# Air_SCHv3.net
KiCad netlist of a schematic drawn in Altium Designer
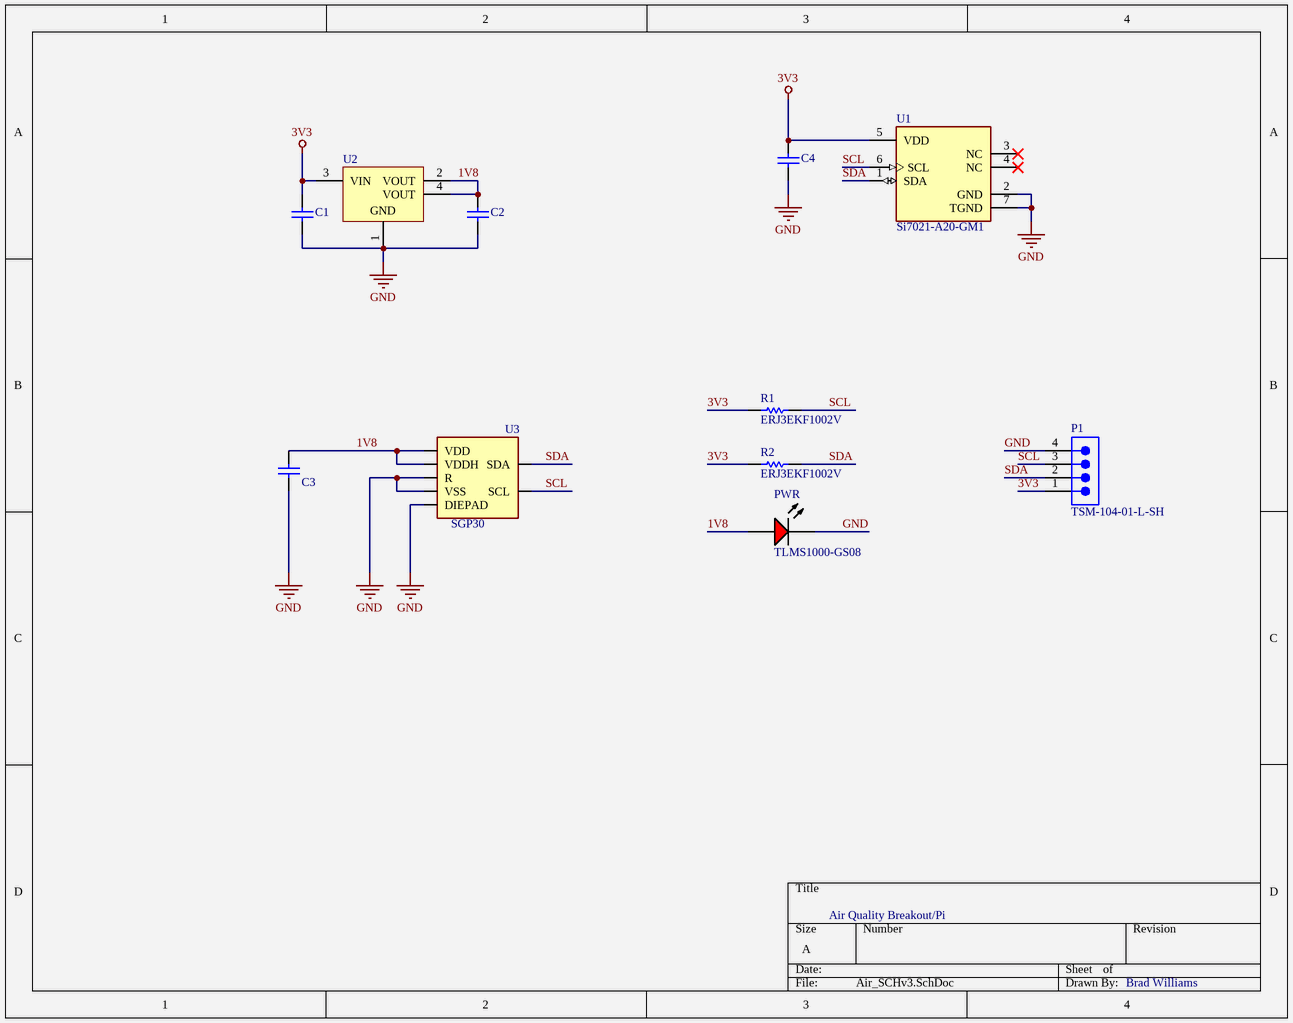
[diagram p0: Air_SCHv3.SchDoc]

(export (version "E")
  (design (tool "Eeschema 10.0.6"))
  (components
    (comp (ref "C1")
      (value "CGA3E2X7R1H104K080AA")
      (footprint "CAPC1608X90X20LL10")
      (description "Chip Capacitor, 0.1 uF, +/- 10%, 50 V, -55 to 125 degC, 0603 (1608 Metric), RoHS, Tape and Reel")
      (fields (field (name "VOLTAGE") "50V") (field (name "TOLERANCE") "10%"))
      (libsource (lib "Altium Content Vault") (part "CAP-NP-2"))
    )
    (comp (ref "C2")
      (value "GCM21BR70J106KE22L")
      (footprint "CAPC2013X140X45LL15T25")
      (fields (field (name "MANUFACTURER") "Murata"))
      (libsource (lib "Altium Content Vault") (part "CAP"))
    )
    (comp (ref "C3")
      (value "CGA3E2X7R1H104K080AA")
      (footprint "CAPC1608X90X20LL10")
      (description "Chip Capacitor, 0.1 uF, +/- 10%, 50 V, -55 to 125 degC, 0603 (1608 Metric), RoHS, Tape and Reel")
      (fields (field (name "VOLTAGE") "50V") (field (name "TOLERANCE") "10%"))
      (libsource (lib "Altium Content Vault") (part "CAP-NP-2"))
    )
    (comp (ref "C4")
      (value "CGA3E2X7R1H104K080AA")
      (footprint "CAPC1608X90X20LL10")
      (description "Chip Capacitor, 0.1 uF, +/- 10%, 50 V, -55 to 125 degC, 0603 (1608 Metric), RoHS, Tape and Reel")
      (fields (field (name "VOLTAGE") "50V") (field (name "TOLERANCE") "10%"))
      (libsource (lib "Altium Content Vault") (part "CAP-NP-2"))
    )
    (comp (ref "P1")
      (value "TSM-104-01-L-SH")
      (footprint "SMTC-TSM-104-01-X-SH")
      (fields (field (name "MANUFACTURER") "Samtec"))
      (libsource (lib "Altium Content Vault") (part "SMTC-TSM-104-01-X-SH"))
    )
    (comp (ref "PWR")
      (value "TLMS1000-GS08")
      (footprint "VISH-TLMS1000_V")
      (description "Low Current LED, 40 mW, 1.8 V, -40 to 100 degC, 2-Pin SMD (0603), RoHS, Tape and Reel")
      (fields (field (name "MANUFACTURER") "Vishay"))
      (libsource (lib "Altium Content Vault") (part "LED-RED-AK-2"))
    )
    (comp (ref "R1")
      (value "ERJ3EKF1002V")
      (footprint "RESC1609X55X30LL15T15")
      (description "Chip Resistor, 10 KOhm, +/- 1%, 0.1 W, -55 to 155 degC, 0603 (1608 Metric), RoHS, Tape and Reel")
      (fields (field (name "TOLERANCE") "1%") (field (name "MANUFACTURER") "Panasonic"))
      (libsource (lib "Altium Content Vault") (part "RES-2"))
    )
    (comp (ref "R2")
      (value "ERJ3EKF1002V")
      (footprint "RESC1609X55X30LL15T15")
      (description "Chip Resistor, 10 KOhm, +/- 1%, 0.1 W, -55 to 155 degC, 0603 (1608 Metric), RoHS, Tape and Reel")
      (fields (field (name "TOLERANCE") "1%") (field (name "MANUFACTURER") "Panasonic"))
      (libsource (lib "Altium Content Vault") (part "RES-2"))
    )
    (comp (ref "U1")
      (value "Si7021-A20-GM1")
      (footprint "FP-Si7021-A20-GM1-MFG")
      (description "SENS HUMI/TEMP 3.6V I2C 3% 6DFN")
      (libsource (lib "Altium Content Vault") (part "6f1d054818c6c7d664b89c5ab42d61f"))
    )
    (comp (ref "U2")
      (value "LD1117AS18TR")
      (footprint "SOT-223_L")
      (description "1A, Low Drop Positive Voltage Regulator, 1.8V, 4-Pin SOT-223, Tape and Reel")
      (libsource (lib "Altium Content Vault") (part "PM-REG-LD1117-SOT4"))
    )
    (comp (ref "U3")
      (value "SGP30")
      (footprint "SGP30")
      (description "AIR QUALITY GAS SENSOR FOR VOC'S")
      (fields (field (name "MF") "Sensirion AG"))
      (libsource (lib "Brad Williams") (part "SGP30"))
    )
  )
  (nets
    (net (code "1") (name "/1V8") (class "Default")
      (node (ref "C2") (pin "2") (pinfunction "2_2") (pintype "passive"))
      (node (ref "C3") (pin "2") (pinfunction "2_2") (pintype "passive"))
      (node (ref "PWR") (pin "1") (pinfunction "A_1") (pintype "passive"))
      (node (ref "U2") (pin "2") (pinfunction "VOUT_2") (pintype "power_in"))
      (node (ref "U2") (pin "4") (pinfunction "VOUT_4") (pintype "power_in"))
      (node (ref "U3") (pin "1") (pinfunction "VDD_1") (pintype "bidirectional"))
      (node (ref "U3") (pin "5") (pinfunction "VDDH_5") (pintype "bidirectional"))
    )
    (net (code "2") (name "/SCL") (class "Default")
      (node (ref "P1") (pin "3") (pinfunction "3_3") (pintype "passive"))
      (node (ref "R1") (pin "2") (pinfunction "2_2") (pintype "passive"))
      (node (ref "U1") (pin "6") (pinfunction "SCL_6") (pintype "input"))
      (node (ref "U3") (pin "6") (pinfunction "SCL_6") (pintype "bidirectional"))
    )
    (net (code "3") (name "/SDA") (class "Default")
      (node (ref "P1") (pin "2") (pinfunction "2_2") (pintype "passive"))
      (node (ref "R2") (pin "2") (pinfunction "2_2") (pintype "passive"))
      (node (ref "U1") (pin "1") (pinfunction "SDA_1") (pintype "bidirectional"))
      (node (ref "U3") (pin "3") (pinfunction "SDA_3") (pintype "bidirectional"))
    )
    (net (code "4") (name "3V3") (class "Default")
      (node (ref "C1") (pin "2") (pinfunction "2_2") (pintype "passive"))
      (node (ref "C4") (pin "2") (pinfunction "2_2") (pintype "passive"))
      (node (ref "P1") (pin "1") (pinfunction "1_1") (pintype "passive"))
      (node (ref "R1") (pin "1") (pinfunction "1_1") (pintype "passive"))
      (node (ref "R2") (pin "1") (pinfunction "1_1") (pintype "passive"))
      (node (ref "U1") (pin "5") (pinfunction "VDD_5") (pintype "power_in"))
      (node (ref "U2") (pin "3") (pinfunction "VIN_3") (pintype "power_in"))
    )
    (net (code "5") (name "GND") (class "Default")
      (node (ref "C1") (pin "1") (pinfunction "1_1") (pintype "passive"))
      (node (ref "C2") (pin "1") (pinfunction "1_1") (pintype "passive"))
      (node (ref "C3") (pin "1") (pinfunction "1_1") (pintype "passive"))
      (node (ref "C4") (pin "1") (pinfunction "1_1") (pintype "passive"))
      (node (ref "P1") (pin "4") (pinfunction "4_4") (pintype "passive"))
      (node (ref "PWR") (pin "2") (pinfunction "K_2") (pintype "passive"))
      (node (ref "U1") (pin "2") (pinfunction "GND_2") (pintype "power_in"))
      (node (ref "U1") (pin "7") (pinfunction "TGND_7") (pintype "power_in"))
      (node (ref "U2") (pin "1") (pinfunction "GND_1") (pintype "power_in"))
      (node (ref "U3") (pin "2") (pinfunction "VSS_2") (pintype "bidirectional"))
      (node (ref "U3") (pin "4") (pinfunction "R_4") (pintype "bidirectional"))
      (node (ref "U3") (pin "DIEPAD") (pinfunction "DIEPAD_DIEPAD") (pintype "bidirectional"))
    )
    (net (code "6") (name "unconnected-(U1-NC-Pad3)") (class "Default")
      (node (ref "U1") (pin "3") (pinfunction "NC_3") (pintype "passive+no_connect"))
    )
    (net (code "7") (name "unconnected-(U1-NC-Pad4)") (class "Default")
      (node (ref "U1") (pin "4") (pinfunction "NC_4") (pintype "passive+no_connect"))
    )
  )
)
